# dwm1001.net
KiCad netlist of a schematic drawn in Altium Designer
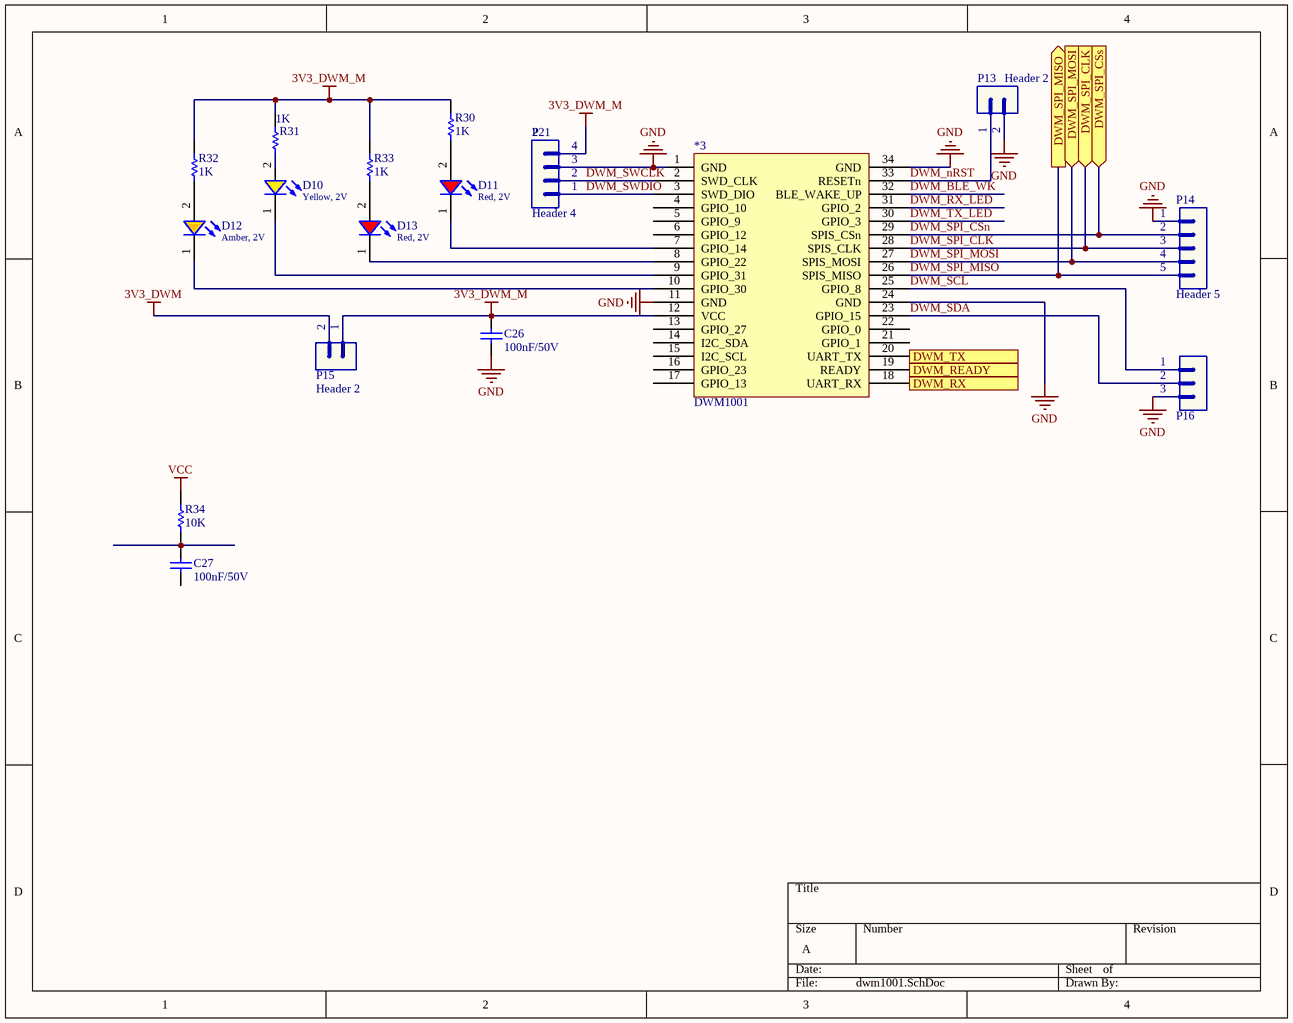
[diagram p0: dwm1001.SchDoc]

(export (version "E")
  (design (tool "Eeschema 10.0.6"))
  (components
    (comp (ref "*3") (value "DWM1001") (footprint "DWM1001") (libsource (lib "PIFWRoBot") (part "DWM1001")))
    (comp (ref "2")
      (value "Header 4")
      (footprint "JP4")
      (description "Header, 4-Pin")
      (fields (field (name "PUBLISHER") "Altium Limited"))
      (libsource (lib "integrated_lib") (part "Header 4"))
    )
    (comp (ref "C26")
      (value "100nF/50V")
      (footprint "CAP-SM-0805")
      (description "CAP CER 0.1UF 50V Y5V 0805")
      (fields
        (field (name "MANUFACTURER") "Samsung Electro-Mechanics")
        (field (name "MANUFACTURER PART NUMBER") "CL21F104ZBCNNNC")
      )
      (libsource (lib "Capacitor") (part "Cap-100nF-50V-0805"))
    )
    (comp (ref "C27")
      (value "100nF/50V")
      (footprint "CAP-SM-0805")
      (description "CAP CER 0.1UF 50V Y5V 0805")
      (fields
        (field (name "MANUFACTURER") "Samsung Electro-Mechanics")
        (field (name "MANUFACTURER PART NUMBER") "CL21F104ZBCNNNC")
      )
      (libsource (lib "Capacitor") (part "Cap-100nF-50V-0805"))
    )
    (comp (ref "D10")
      (value "Yellow, 2V")
      (footprint "WL-SMCW_0603_H=0.25mm")
      (description "WL-SMCW SMT Mono-color Chip LED Waterclear, size 0603, Yellow, 2V, 140deg")
      (fields (field (name "PART NUMBER") "150060YS75020") (field (name "PUBLISHER") "Wurth Elektronik"))
      (libsource (lib "150060BS75000_Altium_WL-SMCW_rev20a") (part "150060YS75020"))
    )
    (comp (ref "D11")
      (value "Red, 2V")
      (footprint "WL-SMCW_0603_H=0.25mm")
      (description "WL-SMCW SMT Mono-color Chip LED Waterclear, size 0603, Red, 2V, 140deg")
      (fields (field (name "PART NUMBER") "150060RS75020") (field (name "PUBLISHER") "Wurth Elektronik"))
      (libsource (lib "150060BS75000_Altium_WL-SMCW_rev20a") (part "150060RS75020"))
    )
    (comp (ref "D12")
      (value "Amber, 2V")
      (footprint "WL-SMCW_0603_H=0.25mm")
      (description "WL-SMCW SMT Mono-color Chip LED Waterclear, size 0603, Amber, 2V, 140deg")
      (fields (field (name "PART NUMBER") "150060AS75020") (field (name "PUBLISHER") "Wurth Elektronik"))
      (libsource (lib "150060BS75000_Altium_WL-SMCW_rev20a") (part "150060AS75020"))
    )
    (comp (ref "D13")
      (value "Red, 2V")
      (footprint "WL-SMCW_0603_H=0.25mm")
      (description "WL-SMCW SMT Mono-color Chip LED Waterclear, size 0603, Red, 2V, 140deg")
      (fields (field (name "PART NUMBER") "150060RS75020") (field (name "PUBLISHER") "Wurth Elektronik"))
      (libsource (lib "150060BS75000_Altium_WL-SMCW_rev20a") (part "150060RS75020"))
    )
    (comp (ref "P13")
      (value "Header 2")
      (footprint "JP2")
      (description "Header, 2-Pin")
      (fields (field (name "PUBLISHER") "Altium Limited"))
      (libsource (lib "") (part "Header 2_1"))
    )
    (comp (ref "P14")
      (value "Header 5")
      (footprint "JP5")
      (description "Header, 5-Pin")
      (fields (field (name "PUBLISHER") "Altium Limited"))
      (libsource (lib "integrated_lib") (part "Header 5"))
    )
    (comp (ref "P15")
      (value "Header 2")
      (footprint "JP2")
      (description "Header, 2-Pin")
      (fields (field (name "PUBLISHER") "Altium Limited"))
      (libsource (lib "integrated_lib") (part "Header 2"))
    )
    (comp (ref "P16")
      (value "Header 3")
      (footprint "JP3")
      (description "Header, 3-Pin")
      (fields (field (name "PUBLISHER") "Altium Limited"))
      (libsource (lib "integrated_lib") (part "Header 3"))
    )
    (comp (ref "R30")
      (value "1K")
      (footprint "Resistor:RES-SM-0805")
      (description "RES 1K OHM 1% 1/4W 0805")
      (fields
        (field (name "MANUFACTURER") "Stackpole Electronics Inc")
        (field (name "MANUFACTURER PART NUMBER") "RNCP0805FTD1K00")
      )
      (libsource (lib "Resistor") (part "Res-1K-0805"))
    )
    (comp (ref "R31")
      (value "1K")
      (footprint "Resistor:RES-SM-0805")
      (description "RES 1K OHM 1% 1/4W 0805")
      (fields
        (field (name "MANUFACTURER") "Stackpole Electronics Inc")
        (field (name "MANUFACTURER PART NUMBER") "RNCP0805FTD1K00")
      )
      (libsource (lib "Resistor") (part "Res-1K-0805"))
    )
    (comp (ref "R32")
      (value "1K")
      (footprint "Resistor:RES-SM-0805")
      (description "RES 1K OHM 1% 1/4W 0805")
      (fields
        (field (name "MANUFACTURER") "Stackpole Electronics Inc")
        (field (name "MANUFACTURER PART NUMBER") "RNCP0805FTD1K00")
      )
      (libsource (lib "Resistor") (part "Res-1K-0805"))
    )
    (comp (ref "R33")
      (value "1K")
      (footprint "Resistor:RES-SM-0805")
      (description "RES 1K OHM 1% 1/4W 0805")
      (fields
        (field (name "MANUFACTURER") "Stackpole Electronics Inc")
        (field (name "MANUFACTURER PART NUMBER") "RNCP0805FTD1K00")
      )
      (libsource (lib "Resistor") (part "Res-1K-0805"))
    )
    (comp (ref "R34")
      (value "10K")
      (footprint "Resistor:RES-SM-0805")
      (description "RES 10K OHM 1% 1/4W 0805")
      (fields
        (field (name "MANUFACTURER") "Stackpole Electronics Inc")
        (field (name "MANUFACTURER PART NUMBER") "RNCP0805FTD10K0")
      )
      (libsource (lib "Resistor") (part "Res-10k-0805"))
    )
  )
  (nets
    (net (code "1") (name "/DWM_BLE_WK") (class "Default")
      (node (ref "*3") (pin "32") (pinfunction "BLE_WAKE_UP_32") (pintype "passive"))
    )
    (net (code "2") (name "/DWM_READY") (class "Default")
      (node (ref "*3") (pin "19") (pinfunction "READY_19") (pintype "passive"))
    )
    (net (code "3") (name "/DWM_RX") (class "Default")
      (node (ref "*3") (pin "18") (pinfunction "UART_RX_18") (pintype "passive"))
    )
    (net (code "4") (name "/DWM_RX_LED") (class "Default")
      (node (ref "*3") (pin "31") (pinfunction "GPIO_2_31") (pintype "passive"))
    )
    (net (code "5") (name "/DWM_SCL") (class "Default")
      (node (ref "*3") (pin "25") (pinfunction "GPIO_8_25") (pintype "passive"))
      (node (ref "P16") (pin "1") (pinfunction "1_1") (pintype "passive"))
    )
    (net (code "6") (name "/DWM_SDA") (class "Default")
      (node (ref "*3") (pin "23") (pinfunction "GPIO_15_23") (pintype "passive"))
      (node (ref "P16") (pin "2") (pinfunction "2_2") (pintype "passive"))
    )
    (net (code "7") (name "/DWM_SPI_CLK") (class "Default")
      (node (ref "*3") (pin "28") (pinfunction "SPIS_CLK_28") (pintype "passive"))
      (node (ref "P14") (pin "3") (pinfunction "3_3") (pintype "passive"))
    )
    (net (code "8") (name "/DWM_SPI_CSn") (class "Default")
      (node (ref "*3") (pin "29") (pinfunction "SPIS_CSn_29") (pintype "passive"))
      (node (ref "P14") (pin "2") (pinfunction "2_2") (pintype "passive"))
    )
    (net (code "9") (name "/DWM_SPI_MISO") (class "Default")
      (node (ref "*3") (pin "26") (pinfunction "SPIS_MISO_26") (pintype "passive"))
      (node (ref "P14") (pin "5") (pinfunction "5_5") (pintype "passive"))
    )
    (net (code "10") (name "/DWM_SPI_MOSI") (class "Default")
      (node (ref "*3") (pin "27") (pinfunction "SPIS_MOSI_27") (pintype "passive"))
      (node (ref "P14") (pin "4") (pinfunction "4_4") (pintype "passive"))
    )
    (net (code "11") (name "/DWM_SWCLK") (class "Default")
      (node (ref "*3") (pin "2") (pinfunction "SWD_CLK_2") (pintype "passive"))
      (node (ref "2") (pin "2") (pinfunction "2_2") (pintype "passive"))
    )
    (net (code "12") (name "/DWM_SWDIO") (class "Default")
      (node (ref "*3") (pin "3") (pinfunction "SWD_DIO_3") (pintype "passive"))
      (node (ref "2") (pin "1") (pinfunction "1_1") (pintype "passive"))
    )
    (net (code "13") (name "/DWM_TX") (class "Default")
      (node (ref "*3") (pin "20") (pinfunction "UART_TX_20") (pintype "passive"))
    )
    (net (code "14") (name "/DWM_TX_LED") (class "Default")
      (node (ref "*3") (pin "30") (pinfunction "GPIO_3_30") (pintype "passive"))
    )
    (net (code "15") (name "/DWM_nRST") (class "Default")
      (node (ref "*3") (pin "33") (pinfunction "RESETn_33") (pintype "passive"))
      (node (ref "P13") (pin "1") (pinfunction "1_1") (pintype "passive"))
    )
    (net (code "16") (name "3V3_DWM") (class "Default")
      (node (ref "P15") (pin "2") (pinfunction "2_2") (pintype "passive"))
    )
    (net (code "17") (name "3V3_DWM_M") (class "Default")
      (node (ref "*3") (pin "12") (pinfunction "VCC_12") (pintype "passive"))
      (node (ref "2") (pin "4") (pinfunction "4_4") (pintype "passive"))
      (node (ref "C26") (pin "2") (pinfunction "2_2") (pintype "passive"))
      (node (ref "P15") (pin "1") (pinfunction "1_1") (pintype "passive"))
      (node (ref "R30") (pin "2") (pinfunction "2_2") (pintype "passive"))
      (node (ref "R31") (pin "2") (pinfunction "2_2") (pintype "passive"))
      (node (ref "R32") (pin "2") (pinfunction "2_2") (pintype "passive"))
      (node (ref "R33") (pin "2") (pinfunction "2_2") (pintype "passive"))
    )
    (net (code "18") (name "GND") (class "Default")
      (node (ref "*3") (pin "1") (pinfunction "GND_1") (pintype "passive"))
      (node (ref "*3") (pin "11") (pinfunction "GND_11") (pintype "passive"))
      (node (ref "*3") (pin "24") (pinfunction "GND_24") (pintype "passive"))
      (node (ref "*3") (pin "34") (pinfunction "GND_34") (pintype "passive"))
      (node (ref "2") (pin "3") (pinfunction "3_3") (pintype "passive"))
      (node (ref "C26") (pin "1") (pinfunction "1_1") (pintype "passive"))
      (node (ref "P13") (pin "2") (pinfunction "2_2") (pintype "passive"))
      (node (ref "P14") (pin "1") (pinfunction "1_1") (pintype "passive"))
      (node (ref "P16") (pin "3") (pinfunction "3_3") (pintype "passive"))
    )
    (net (code "19") (name "Net-(*3-GPIO_14)") (class "Default")
      (node (ref "*3") (pin "7") (pinfunction "GPIO_14_7") (pintype "passive"))
      (node (ref "D11") (pin "1") (pinfunction "K_1") (pintype "passive"))
    )
    (net (code "20") (name "Net-(*3-GPIO_22)") (class "Default")
      (node (ref "*3") (pin "8") (pinfunction "GPIO_22_8") (pintype "passive"))
      (node (ref "D13") (pin "1") (pinfunction "K_1") (pintype "passive"))
    )
    (net (code "21") (name "Net-(*3-GPIO_30)") (class "Default")
      (node (ref "*3") (pin "10") (pinfunction "GPIO_30_10") (pintype "passive"))
      (node (ref "D12") (pin "1") (pinfunction "K_1") (pintype "passive"))
    )
    (net (code "22") (name "Net-(*3-GPIO_31)") (class "Default")
      (node (ref "*3") (pin "9") (pinfunction "GPIO_31_9") (pintype "passive"))
      (node (ref "D10") (pin "1") (pinfunction "K_1") (pintype "passive"))
    )
    (net (code "23") (name "Net-(C27-Pad2)") (class "Default")
      (node (ref "C27") (pin "2") (pinfunction "2_2") (pintype "passive"))
      (node (ref "R34") (pin "1") (pinfunction "1_1") (pintype "passive"))
    )
    (net (code "24") (name "Net-(D10-A)") (class "Default")
      (node (ref "D10") (pin "2") (pinfunction "A_2") (pintype "passive"))
      (node (ref "R31") (pin "1") (pinfunction "1_1") (pintype "passive"))
    )
    (net (code "25") (name "Net-(D11-A)") (class "Default")
      (node (ref "D11") (pin "2") (pinfunction "A_2") (pintype "passive"))
      (node (ref "R30") (pin "1") (pinfunction "1_1") (pintype "passive"))
    )
    (net (code "26") (name "Net-(D12-A)") (class "Default")
      (node (ref "D12") (pin "2") (pinfunction "A_2") (pintype "passive"))
      (node (ref "R32") (pin "1") (pinfunction "1_1") (pintype "passive"))
    )
    (net (code "27") (name "Net-(D13-A)") (class "Default")
      (node (ref "D13") (pin "2") (pinfunction "A_2") (pintype "passive"))
      (node (ref "R33") (pin "1") (pinfunction "1_1") (pintype "passive"))
    )
    (net (code "28") (name "VCC") (class "Default")
      (node (ref "R34") (pin "2") (pinfunction "2_2") (pintype "passive"))
    )
    (net (code "29") (name "unconnected-(*3-GPIO_0-Pad22)") (class "Default")
      (node (ref "*3") (pin "22") (pinfunction "GPIO_0_22") (pintype "passive"))
    )
    (net (code "30") (name "unconnected-(*3-GPIO_1-Pad21)") (class "Default")
      (node (ref "*3") (pin "21") (pinfunction "GPIO_1_21") (pintype "passive"))
    )
    (net (code "31") (name "unconnected-(*3-GPIO_9-Pad5)") (class "Default")
      (node (ref "*3") (pin "5") (pinfunction "GPIO_9_5") (pintype "passive"))
    )
    (net (code "32") (name "unconnected-(*3-GPIO_10-Pad4)") (class "Default")
      (node (ref "*3") (pin "4") (pinfunction "GPIO_10_4") (pintype "passive"))
    )
    (net (code "33") (name "unconnected-(*3-GPIO_12-Pad6)") (class "Default")
      (node (ref "*3") (pin "6") (pinfunction "GPIO_12_6") (pintype "passive"))
    )
    (net (code "34") (name "unconnected-(*3-GPIO_13-Pad17)") (class "Default")
      (node (ref "*3") (pin "17") (pinfunction "GPIO_13_17") (pintype "passive"))
    )
    (net (code "35") (name "unconnected-(*3-GPIO_23-Pad16)") (class "Default")
      (node (ref "*3") (pin "16") (pinfunction "GPIO_23_16") (pintype "passive"))
    )
    (net (code "36") (name "unconnected-(*3-GPIO_27-Pad13)") (class "Default")
      (node (ref "*3") (pin "13") (pinfunction "GPIO_27_13") (pintype "passive"))
    )
    (net (code "37") (name "unconnected-(*3-I2C_SCL-Pad15)") (class "Default")
      (node (ref "*3") (pin "15") (pinfunction "I2C_SCL_15") (pintype "passive"))
    )
    (net (code "38") (name "unconnected-(*3-I2C_SDA-Pad14)") (class "Default")
      (node (ref "*3") (pin "14") (pinfunction "I2C_SDA_14") (pintype "passive"))
    )
    (net (code "39") (name "unconnected-(C27-Pad1)") (class "Default")
      (node (ref "C27") (pin "1") (pinfunction "1_1") (pintype "passive"))
    )
  )
)
